# ethernet_poe.net
KiCad netlist of a schematic drawn in EAGLE
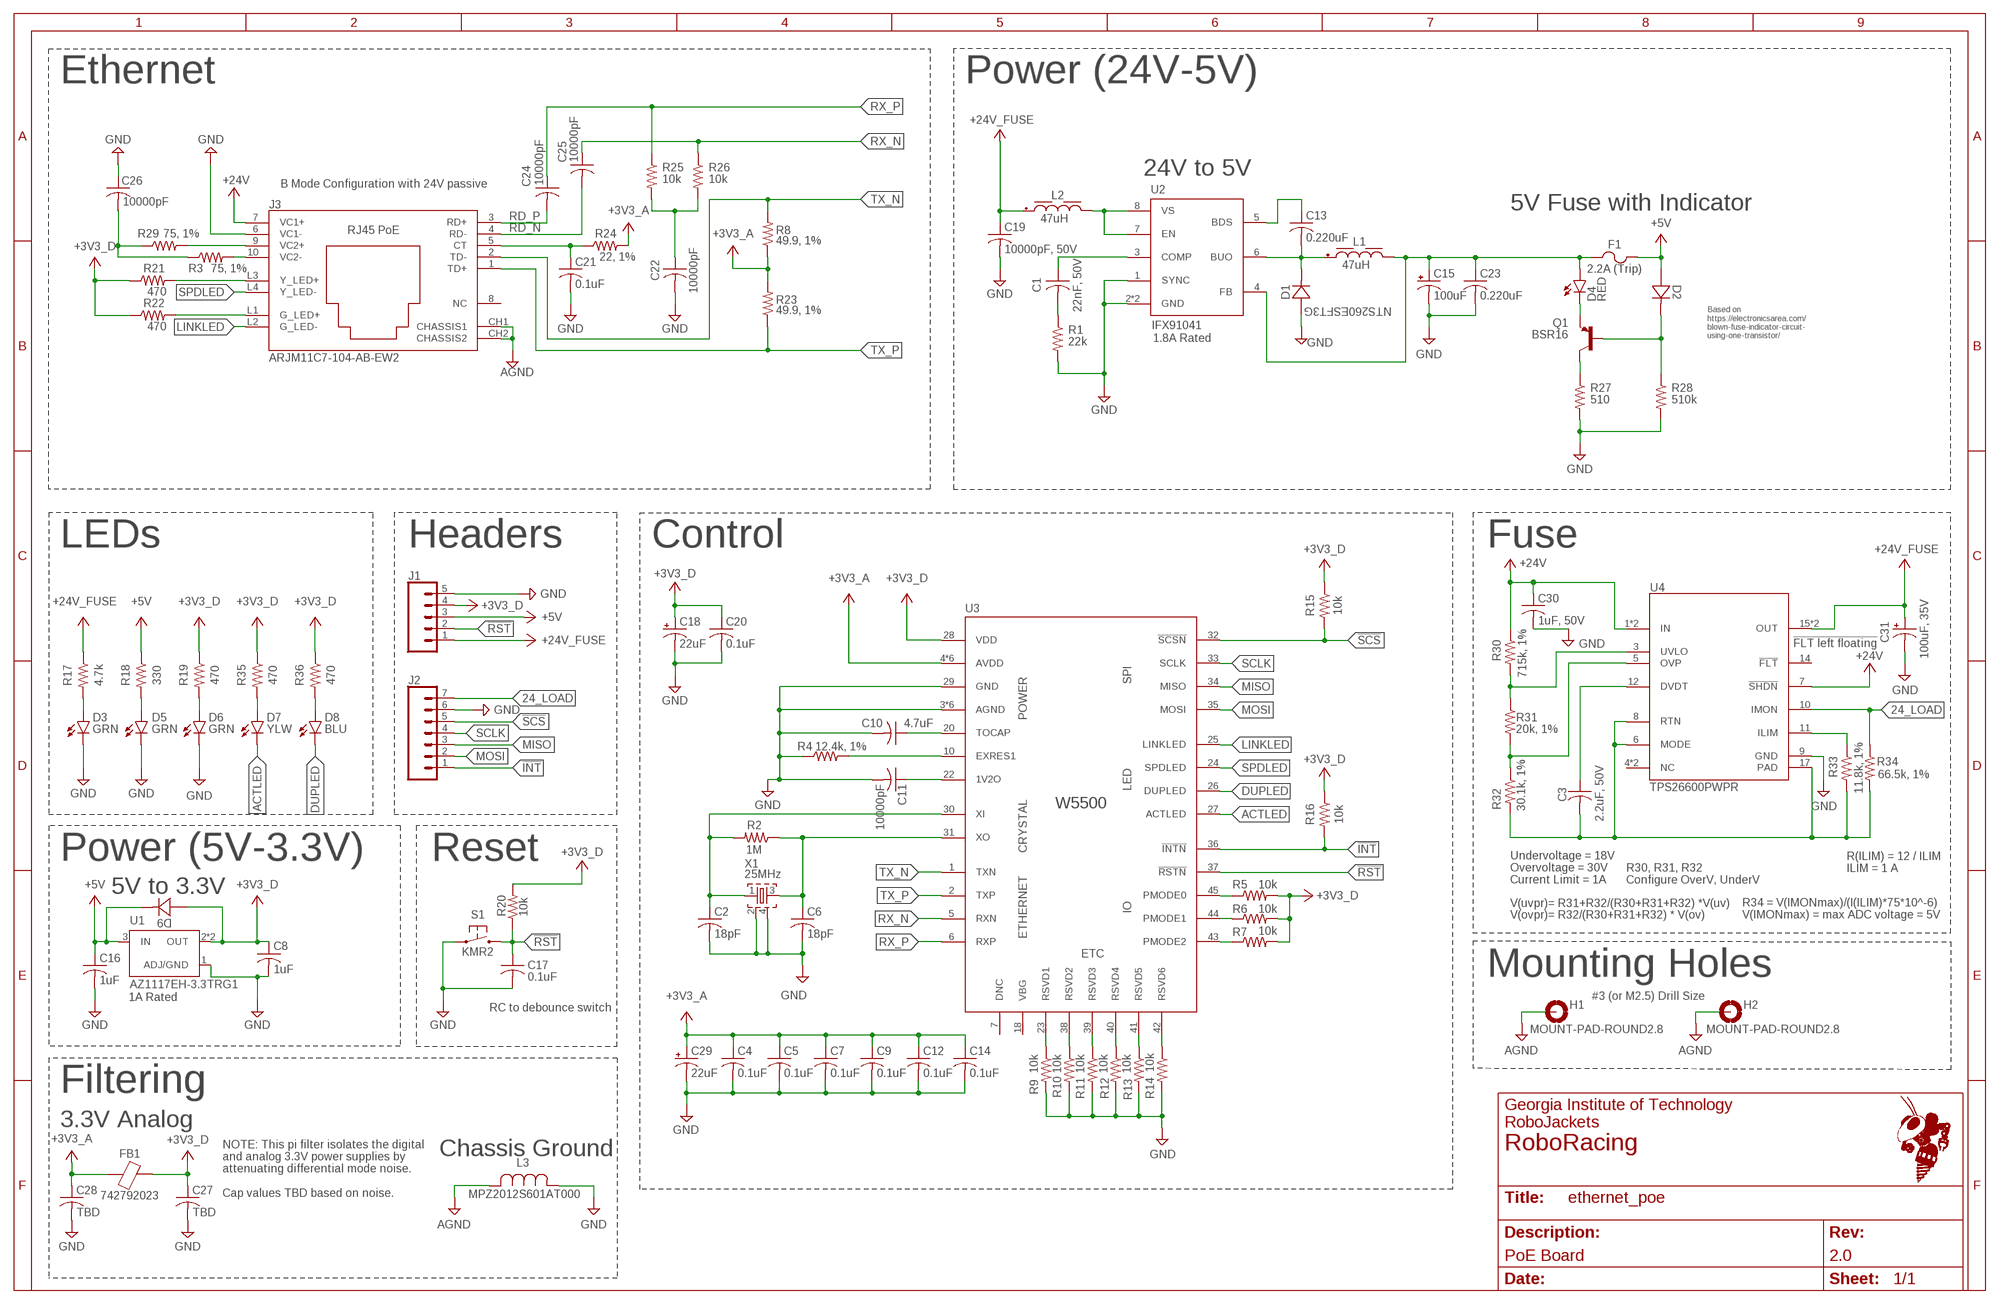
[diagram p0: schematic, sheet 1]

(export (version "E")
  (design (tool "Eeschema 10.0.6"))
  (components
    (comp (ref "C1")
      (value "22nF, 50V")
      (footprint "eagle-import:C0603")
      (libsource (lib "eagle-import") (part "rcl_334_C-USC0603"))
    )
    (comp (ref "C2")
      (value "18pF")
      (footprint "eagle-import:C0603")
      (libsource (lib "eagle-import") (part "rcl_334_C-USC0603"))
    )
    (comp (ref "C3")
      (value "2.2uF, 50V")
      (footprint "eagle-import:C0603")
      (libsource (lib "eagle-import") (part "rcl_334_C-USC0603"))
    )
    (comp (ref "C4")
      (value "0.1uF")
      (footprint "eagle-import:C0402")
      (libsource (lib "eagle-import") (part "C-USC0402"))
    )
    (comp (ref "C5")
      (value "0.1uF")
      (footprint "eagle-import:C0402")
      (libsource (lib "eagle-import") (part "C-USC0402"))
    )
    (comp (ref "C6")
      (value "18pF")
      (footprint "eagle-import:C0603")
      (libsource (lib "eagle-import") (part "rcl_334_C-USC0603"))
    )
    (comp (ref "C7")
      (value "0.1uF")
      (footprint "eagle-import:C0402")
      (libsource (lib "eagle-import") (part "C-USC0402"))
    )
    (comp (ref "C8")
      (value "1uF")
      (footprint "eagle-import:C0603")
      (libsource (lib "eagle-import") (part "rcl_334_C-USC0603"))
    )
    (comp (ref "C9")
      (value "0.1uF")
      (footprint "eagle-import:C0402")
      (libsource (lib "eagle-import") (part "C-USC0402"))
    )
    (comp (ref "C10")
      (value "4.7uF")
      (footprint "eagle-import:C0603")
      (libsource (lib "eagle-import") (part "rcl_334_C-USC0603"))
    )
    (comp (ref "C11")
      (value "10000pF")
      (footprint "eagle-import:C0402")
      (libsource (lib "eagle-import") (part "C-USC0402"))
    )
    (comp (ref "C12")
      (value "0.1uF")
      (footprint "eagle-import:C0402")
      (libsource (lib "eagle-import") (part "C-USC0402"))
    )
    (comp (ref "C13")
      (value "0.220uF")
      (footprint "eagle-import:C0603")
      (libsource (lib "eagle-import") (part "rcl_334_C-USC0603"))
    )
    (comp (ref "C14")
      (value "0.1uF")
      (footprint "eagle-import:C0402")
      (libsource (lib "eagle-import") (part "C-USC0402"))
    )
    (comp (ref "C15")
      (value "100uF")
      (footprint "eagle-import:E2-5")
      (libsource (lib "eagle-import") (part "CPOL-USE2-5"))
    )
    (comp (ref "C16")
      (value "1uF")
      (footprint "eagle-import:C0603")
      (libsource (lib "eagle-import") (part "rcl_334_C-USC0603"))
    )
    (comp (ref "C17")
      (value "0.1uF")
      (footprint "eagle-import:C0603")
      (libsource (lib "eagle-import") (part "rcl_334_C-USC0603"))
    )
    (comp (ref "C18")
      (value "22uF")
      (footprint "eagle-import:E2-5")
      (libsource (lib "eagle-import") (part "CPOL-USE2-5"))
    )
    (comp (ref "C19")
      (value "10000pF, 50V")
      (footprint "eagle-import:C0603")
      (libsource (lib "eagle-import") (part "rcl_334_C-USC0603"))
    )
    (comp (ref "C20")
      (value "0.1uF")
      (footprint "eagle-import:C0603")
      (libsource (lib "eagle-import") (part "rcl_334_C-USC0603"))
    )
    (comp (ref "C21")
      (value "0.1uF")
      (footprint "eagle-import:C0603")
      (libsource (lib "eagle-import") (part "rcl_334_C-USC0603"))
    )
    (comp (ref "C22")
      (value "10000pF")
      (footprint "eagle-import:C0603")
      (libsource (lib "eagle-import") (part "rcl_334_C-USC0603"))
    )
    (comp (ref "C23")
      (value "0.220uF")
      (footprint "eagle-import:C0603")
      (libsource (lib "eagle-import") (part "rcl_334_C-USC0603"))
    )
    (comp (ref "C24")
      (value "10000pF")
      (footprint "eagle-import:C0402")
      (libsource (lib "eagle-import") (part "C-USC0402"))
    )
    (comp (ref "C25")
      (value "10000pF")
      (footprint "eagle-import:C0402")
      (libsource (lib "eagle-import") (part "C-USC0402"))
    )
    (comp (ref "C26")
      (value "10000pF")
      (footprint "eagle-import:C0603")
      (libsource (lib "eagle-import") (part "rcl_334_C-USC0603"))
    )
    (comp (ref "C27")
      (value "TBD")
      (footprint "eagle-import:C0603")
      (libsource (lib "eagle-import") (part "C-USC0603"))
    )
    (comp (ref "C28")
      (value "TBD")
      (footprint "eagle-import:C0603")
      (libsource (lib "eagle-import") (part "C-USC0603"))
    )
    (comp (ref "C29")
      (value "22uF")
      (footprint "eagle-import:PANASONIC_C")
      (libsource (lib "eagle-import") (part "22UF-POLAR-PANASONIC_C-35V-20%"))
    )
    (comp (ref "C30")
      (value "1uF, 50V")
      (footprint "eagle-import:C0603")
      (libsource (lib "eagle-import") (part "rcl_334_C-USC0603"))
    )
    (comp (ref "C31")
      (value "100uF, 35V")
      (footprint "eagle-import:E2-5")
      (libsource (lib "eagle-import") (part "CPOL-USE2-5"))
    )
    (comp (ref "D1")
      (value "NTS260ESFT3G")
      (footprint "eagle-import:DIO_SS26FL")
      (libsource (lib "eagle-import") (part "NTS260ESFT3G"))
    )
    (comp (ref "D2")
      (value "1N4148W-7-F")
      (footprint "eagle-import:SOD123_DIO")
      (libsource (lib "eagle-import") (part "1N4148W-7-F"))
    )
    (comp (ref "D3")
      (value "GRN")
      (footprint "eagle-import:CHIP-LED0603")
      (libsource (lib "eagle-import") (part "LEDCHIP-LED0603"))
    )
    (comp (ref "D4")
      (value "RED")
      (footprint "eagle-import:CHIP-LED0603")
      (libsource (lib "eagle-import") (part "LEDCHIP-LED0603"))
    )
    (comp (ref "D5")
      (value "GRN")
      (footprint "eagle-import:CHIP-LED0603")
      (libsource (lib "eagle-import") (part "LEDCHIP-LED0603"))
    )
    (comp (ref "D6")
      (value "GRN")
      (footprint "eagle-import:CHIP-LED0603")
      (libsource (lib "eagle-import") (part "LEDCHIP-LED0603"))
    )
    (comp (ref "D7")
      (value "YLW")
      (footprint "eagle-import:CHIP-LED0603")
      (libsource (lib "eagle-import") (part "LEDCHIP-LED0603"))
    )
    (comp (ref "D8")
      (value "BLU")
      (footprint "eagle-import:CHIP-LED0603")
      (libsource (lib "eagle-import") (part "LEDCHIP-LED0603"))
    )
    (comp (ref "D9")
      (value "1N4148W-7-F")
      (footprint "eagle-import:SOD123_DIO")
      (libsource (lib "eagle-import") (part "1N4148W-7-F"))
    )
    (comp (ref "F1")
      (value "2.2A (Trip)")
      (footprint "eagle-import:0ZCG_BEL")
      (libsource (lib "eagle-import") (part "0ZCG0110AF2C"))
    )
    (comp (ref "FB1")
      (value "742792023")
      (footprint "eagle-import:0805")
      (libsource (lib "eagle-import") (part "742792023"))
    )
    (comp (ref "H1")
      (value "MOUNT-PAD-ROUND2.8")
      (footprint "eagle-import:2,8-PAD")
      (libsource (lib "eagle-import") (part "MOUNT-PAD-ROUND2.8"))
    )
    (comp (ref "H2")
      (value "MOUNT-PAD-ROUND2.8")
      (footprint "eagle-import:2,8-PAD")
      (libsource (lib "eagle-import") (part "MOUNT-PAD-ROUND2.8"))
    )
    (comp (ref "J1")
      (value "CONN_05")
      (footprint "eagle-import:1X05")
      (libsource (lib "eagle-import") (part "CONN_05"))
    )
    (comp (ref "J2")
      (value "CONN_07")
      (footprint "eagle-import:1X07")
      (libsource (lib "eagle-import") (part "CONN_07"))
    )
    (comp (ref "J3")
      (value "ARJM11C7-104-AB-EW2")
      (footprint "eagle-import:CONN_EW_ABR")
      (libsource (lib "eagle-import") (part "ARJM11C7-104-AB-EW2"))
    )
    (comp (ref "L1")
      (value "47uH")
      (footprint "eagle-import:WE-PD_1260")
      (libsource (lib "eagle-import") (part "WE-PD_1260_744771147"))
    )
    (comp (ref "L2")
      (value "47uH")
      (footprint "eagle-import:WE-PD_7345")
      (libsource (lib "eagle-import") (part "WE-PD_7345_744777147"))
    )
    (comp (ref "L3")
      (value "MPZ2012S601AT000")
      (footprint "eagle-import:IND_2012_TDK")
      (libsource (lib "eagle-import") (part "MPZ2012S601AT000"))
    )
    (comp (ref "Q1")
      (value "BSR16")
      (footprint "eagle-import:SOT-23-3")
      (libsource (lib "eagle-import") (part "BSR16"))
    )
    (comp (ref "R1")
      (value "22k")
      (footprint "eagle-import:R0603")
      (libsource (lib "eagle-import") (part "rcl_334_R-US_R0603"))
    )
    (comp (ref "R2")
      (value "1M")
      (footprint "eagle-import:R0402")
      (libsource (lib "eagle-import") (part "R-US_R0402"))
    )
    (comp (ref "R3")
      (value "75, 1%")
      (footprint "eagle-import:R0603")
      (libsource (lib "eagle-import") (part "rcl_334_R-US_R0603"))
    )
    (comp (ref "R4")
      (value "12.4k, 1%")
      (footprint "eagle-import:R0603")
      (libsource (lib "eagle-import") (part "rcl_334_R-US_R0603"))
    )
    (comp (ref "R5")
      (value "10k")
      (footprint "eagle-import:R0603")
      (libsource (lib "eagle-import") (part "rcl_334_R-US_R0603"))
    )
    (comp (ref "R6")
      (value "10k")
      (footprint "eagle-import:R0603")
      (libsource (lib "eagle-import") (part "rcl_334_R-US_R0603"))
    )
    (comp (ref "R7")
      (value "10k")
      (footprint "eagle-import:R0603")
      (libsource (lib "eagle-import") (part "rcl_334_R-US_R0603"))
    )
    (comp (ref "R8")
      (value "49.9, 1%")
      (footprint "eagle-import:R0402")
      (libsource (lib "eagle-import") (part "R-US_R0402"))
    )
    (comp (ref "R9")
      (value "10k")
      (footprint "eagle-import:R0603")
      (libsource (lib "eagle-import") (part "rcl_334_R-US_R0603"))
    )
    (comp (ref "R10")
      (value "10k")
      (footprint "eagle-import:R0603")
      (libsource (lib "eagle-import") (part "rcl_334_R-US_R0603"))
    )
    (comp (ref "R11")
      (value "10k")
      (footprint "eagle-import:R0603")
      (libsource (lib "eagle-import") (part "rcl_334_R-US_R0603"))
    )
    (comp (ref "R12")
      (value "10k")
      (footprint "eagle-import:R0603")
      (libsource (lib "eagle-import") (part "rcl_334_R-US_R0603"))
    )
    (comp (ref "R13")
      (value "10k")
      (footprint "eagle-import:R0603")
      (libsource (lib "eagle-import") (part "rcl_334_R-US_R0603"))
    )
    (comp (ref "R14")
      (value "10k")
      (footprint "eagle-import:R0603")
      (libsource (lib "eagle-import") (part "rcl_334_R-US_R0603"))
    )
    (comp (ref "R15")
      (value "10k")
      (footprint "eagle-import:R0603")
      (libsource (lib "eagle-import") (part "rcl_334_R-US_R0603"))
    )
    (comp (ref "R16")
      (value "10k")
      (footprint "eagle-import:R0603")
      (libsource (lib "eagle-import") (part "rcl_334_R-US_R0603"))
    )
    (comp (ref "R17")
      (value "4.7k")
      (footprint "eagle-import:R0603")
      (libsource (lib "eagle-import") (part "rcl_334_R-US_R0603"))
    )
    (comp (ref "R18")
      (value "330")
      (footprint "eagle-import:R0603")
      (libsource (lib "eagle-import") (part "rcl_334_R-US_R0603"))
    )
    (comp (ref "R19")
      (value "470")
      (footprint "eagle-import:R0603")
      (libsource (lib "eagle-import") (part "rcl_334_R-US_R0603"))
    )
    (comp (ref "R20")
      (value "10k")
      (footprint "eagle-import:R0603")
      (libsource (lib "eagle-import") (part "rcl_334_R-US_R0603"))
    )
    (comp (ref "R21")
      (value "470")
      (footprint "eagle-import:R0603")
      (libsource (lib "eagle-import") (part "rcl_334_R-US_R0603"))
    )
    (comp (ref "R22")
      (value "470")
      (footprint "eagle-import:R0603")
      (libsource (lib "eagle-import") (part "rcl_334_R-US_R0603"))
    )
    (comp (ref "R23")
      (value "49.9, 1%")
      (footprint "eagle-import:R0402")
      (libsource (lib "eagle-import") (part "R-US_R0402"))
    )
    (comp (ref "R24")
      (value "22, 1%")
      (footprint "eagle-import:R0603")
      (libsource (lib "eagle-import") (part "rcl_334_R-US_R0603"))
    )
    (comp (ref "R25")
      (value "10k")
      (footprint "eagle-import:R0603")
      (libsource (lib "eagle-import") (part "rcl_334_R-US_R0603"))
    )
    (comp (ref "R26")
      (value "10k")
      (footprint "eagle-import:R0603")
      (libsource (lib "eagle-import") (part "rcl_334_R-US_R0603"))
    )
    (comp (ref "R27")
      (value "510")
      (footprint "eagle-import:R0603")
      (libsource (lib "eagle-import") (part "rcl_334_R-US_R0603"))
    )
    (comp (ref "R28")
      (value "510k")
      (footprint "eagle-import:R0603")
      (libsource (lib "eagle-import") (part "rcl_334_R-US_R0603"))
    )
    (comp (ref "R29")
      (value "75, 1%")
      (footprint "eagle-import:R0603")
      (libsource (lib "eagle-import") (part "rcl_334_R-US_R0603"))
    )
    (comp (ref "R30")
      (value "715k, 1%")
      (footprint "eagle-import:R0603")
      (libsource (lib "eagle-import") (part "rcl_334_R-US_R0603"))
    )
    (comp (ref "R31")
      (value "20k, 1%")
      (footprint "eagle-import:R0603")
      (libsource (lib "eagle-import") (part "rcl_334_R-US_R0603"))
    )
    (comp (ref "R32")
      (value "30.1k, 1%")
      (footprint "eagle-import:R0603")
      (libsource (lib "eagle-import") (part "rcl_334_R-US_R0603"))
    )
    (comp (ref "R33")
      (value "11.8k, 1%")
      (footprint "eagle-import:R0603")
      (libsource (lib "eagle-import") (part "rcl_334_R-US_R0603"))
    )
    (comp (ref "R34")
      (value "66.5k, 1%")
      (footprint "eagle-import:R0603")
      (libsource (lib "eagle-import") (part "rcl_334_R-US_R0603"))
    )
    (comp (ref "R35")
      (value "470")
      (footprint "eagle-import:R0603")
      (libsource (lib "eagle-import") (part "rcl_334_R-US_R0603"))
    )
    (comp (ref "R36")
      (value "470")
      (footprint "eagle-import:R0603")
      (libsource (lib "eagle-import") (part "rcl_334_R-US_R0603"))
    )
    (comp (ref "S1")
      (value "KMR2")
      (footprint "eagle-import:KMR2")
      (libsource (lib "eagle-import") (part "KMR2"))
    )
    (comp (ref "U1")
      (value "AZ1117EH-3.3TRG1")
      (footprint "eagle-import:SOT230P700X180-4N")
      (libsource (lib "eagle-import") (part "AZ1117EH-3.3TRG1"))
    )
    (comp (ref "U2")
      (value "IFX91041")
      (footprint "eagle-import:SOIC-8-EXPOSED_PAD")
      (libsource (lib "eagle-import") (part "IFX91041"))
    )
    (comp (ref "U3")
      (value "W5500")
      (footprint "eagle-import:48-LQFP")
      (libsource (lib "eagle-import") (part "W5500"))
    )
    (comp (ref "U4")
      (value "TPS26600PWPR")
      (footprint "eagle-import:PWP0016H_N")
      (libsource (lib "eagle-import") (part "TPS26600PWPR"))
    )
    (comp (ref "X1")
      (value "25MHz")
      (footprint "eagle-import:OSCILLATOR-SMD-2.5X2")
      (libsource (lib "eagle-import") (part "ABM10-25.000MHZ-18-E30-T3"))
    )
  )
  (nets
    (net (code "1") (name "+3V3_A") (class "Default")
      (node (ref "C12") (pin "1") (pinfunction "1_1") (pintype "passive"))
      (node (ref "C14") (pin "1") (pinfunction "1_1") (pintype "passive"))
      (node (ref "C28") (pin "1") (pinfunction "1_1") (pintype "passive"))
      (node (ref "C29") (pin "+") (pinfunction "+_+") (pintype "passive"))
      (node (ref "C4") (pin "1") (pinfunction "1_1") (pintype "passive"))
      (node (ref "C5") (pin "1") (pinfunction "1_1") (pintype "passive"))
      (node (ref "C7") (pin "1") (pinfunction "1_1") (pintype "passive"))
      (node (ref "C9") (pin "1") (pinfunction "1_1") (pintype "passive"))
      (node (ref "FB1") (pin "1") (pinfunction "1_1") (pintype "passive"))
      (node (ref "R23") (pin "2") (pinfunction "2_2") (pintype "passive"))
      (node (ref "R24") (pin "2") (pinfunction "2_2") (pintype "passive"))
      (node (ref "R8") (pin "1") (pinfunction "1_1") (pintype "passive"))
      (node (ref "U3") (pin "11") (pinfunction "AVDD_11") (pintype "power_in"))
      (node (ref "U3") (pin "15") (pinfunction "AVDD_15") (pintype "power_in"))
      (node (ref "U3") (pin "17") (pinfunction "AVDD_17") (pintype "power_in"))
      (node (ref "U3") (pin "21") (pinfunction "AVDD_21") (pintype "power_in"))
      (node (ref "U3") (pin "4") (pinfunction "AVDD_4") (pintype "power_in"))
      (node (ref "U3") (pin "8") (pinfunction "AVDD_8") (pintype "power_in"))
    )
    (net (code "2") (name "+3V3_D") (class "Default")
      (node (ref "C18") (pin "+") (pinfunction "+_+") (pintype "passive"))
      (node (ref "C20") (pin "1") (pinfunction "1_1") (pintype "passive"))
      (node (ref "C27") (pin "1") (pinfunction "1_1") (pintype "passive"))
      (node (ref "C8") (pin "1") (pinfunction "1_1") (pintype "passive"))
      (node (ref "D9") (pin "2") (pinfunction "2_2") (pintype "passive"))
      (node (ref "FB1") (pin "2") (pinfunction "2_2") (pintype "passive"))
      (node (ref "J1") (pin "4") (pinfunction "4_4") (pintype "passive"))
      (node (ref "R15") (pin "1") (pinfunction "1_1") (pintype "passive"))
      (node (ref "R16") (pin "1") (pinfunction "1_1") (pintype "passive"))
      (node (ref "R19") (pin "1") (pinfunction "1_1") (pintype "passive"))
      (node (ref "R20") (pin "2") (pinfunction "2_2") (pintype "passive"))
      (node (ref "R21") (pin "1") (pinfunction "1_1") (pintype "passive"))
      (node (ref "R22") (pin "1") (pinfunction "1_1") (pintype "passive"))
      (node (ref "R35") (pin "1") (pinfunction "1_1") (pintype "passive"))
      (node (ref "R36") (pin "1") (pinfunction "1_1") (pintype "passive"))
      (node (ref "R5") (pin "2") (pinfunction "2_2") (pintype "passive"))
      (node (ref "R6") (pin "2") (pinfunction "2_2") (pintype "passive"))
      (node (ref "R7") (pin "2") (pinfunction "2_2") (pintype "passive"))
      (node (ref "U1") (pin "2") (pinfunction "OUT_2") (pintype "output"))
      (node (ref "U1") (pin "4") (pinfunction "OUT_4") (pintype "output"))
      (node (ref "U3") (pin "28") (pinfunction "VDD_28") (pintype "power_in"))
    )
    (net (code "3") (name "+5V") (class "Default")
      (node (ref "C16") (pin "1") (pinfunction "1_1") (pintype "passive"))
      (node (ref "D2") (pin "2") (pinfunction "2_2") (pintype "passive"))
      (node (ref "D9") (pin "1") (pinfunction "1_1") (pintype "passive"))
      (node (ref "F1") (pin "2") (pinfunction "2_2") (pintype "passive"))
      (node (ref "J1") (pin "3") (pinfunction "3_3") (pintype "passive"))
      (node (ref "R18") (pin "1") (pinfunction "1_1") (pintype "passive"))
      (node (ref "U1") (pin "3") (pinfunction "IN_3") (pintype "input"))
    )
    (net (code "4") (name "+24V") (class "Default")
      (node (ref "C30") (pin "1") (pinfunction "1_1") (pintype "passive"))
      (node (ref "J3") (pin "7") (pinfunction "VC1+_7") (pintype "passive"))
      (node (ref "R30") (pin "1") (pinfunction "1_1") (pintype "passive"))
      (node (ref "U4") (pin "1") (pinfunction "IN_1") (pintype "power_in"))
      (node (ref "U4") (pin "2") (pinfunction "IN_2") (pintype "power_in"))
      (node (ref "U4") (pin "7") (pinfunction "~{SHDN}_7") (pintype "input"))
    )
    (net (code "5") (name "+24V_FUSE") (class "Default")
      (node (ref "C19") (pin "1") (pinfunction "1_1") (pintype "passive"))
      (node (ref "C31") (pin "+") (pinfunction "+_+") (pintype "passive"))
      (node (ref "J1") (pin "1") (pinfunction "1_1") (pintype "passive"))
      (node (ref "L2") (pin "1") (pinfunction "1_1") (pintype "passive"))
      (node (ref "R17") (pin "1") (pinfunction "1_1") (pintype "passive"))
      (node (ref "U4") (pin "15") (pinfunction "OUT_15") (pintype "power_in"))
      (node (ref "U4") (pin "16") (pinfunction "OUT_16") (pintype "power_in"))
    )
    (net (code "6") (name "/RD_N") (class "Default")
      (node (ref "C25") (pin "2") (pinfunction "2_2") (pintype "passive"))
      (node (ref "J3") (pin "4") (pinfunction "RD-_4") (pintype "passive"))
    )
    (net (code "7") (name "/RD_P") (class "Default")
      (node (ref "C24") (pin "2") (pinfunction "2_2") (pintype "passive"))
      (node (ref "J3") (pin "3") (pinfunction "RD+_3") (pintype "passive"))
    )
    (net (code "8") (name "/~{INT}") (class "Default")
      (node (ref "J2") (pin "1") (pinfunction "1_1") (pintype "passive"))
      (node (ref "R16") (pin "2") (pinfunction "2_2") (pintype "passive"))
      (node (ref "U3") (pin "36") (pinfunction "~{INTN}_36") (pintype "output"))
    )
    (net (code "9") (name "/~{RST}") (class "Default")
      (node (ref "C17") (pin "1") (pinfunction "1_1") (pintype "passive"))
      (node (ref "J1") (pin "2") (pinfunction "2_2") (pintype "passive"))
      (node (ref "R20") (pin "1") (pinfunction "1_1") (pintype "passive"))
      (node (ref "S1") (pin "2.1") (pinfunction "2_2.1") (pintype "passive"))
      (node (ref "S1") (pin "2.2") (pinfunction "2_2.2") (pintype "passive"))
      (node (ref "U3") (pin "37") (pinfunction "~{RSTN}_37") (pintype "input"))
    )
    (net (code "10") (name "/~{SCS}") (class "Default")
      (node (ref "J2") (pin "5") (pinfunction "5_5") (pintype "passive"))
      (node (ref "R15") (pin "2") (pinfunction "2_2") (pintype "passive"))
      (node (ref "U3") (pin "32") (pinfunction "~{SCSN}_32") (pintype "input"))
    )
    (net (code "11") (name "24_LOAD") (class "Default")
      (node (ref "J2") (pin "7") (pinfunction "7_7") (pintype "passive"))
      (node (ref "R34") (pin "1") (pinfunction "1_1") (pintype "passive"))
      (node (ref "U4") (pin "10") (pinfunction "IMON_10") (pintype "output"))
    )
    (net (code "12") (name "ACTLED") (class "Default")
      (node (ref "D7") (pin "C") (pinfunction "C_C") (pintype "passive"))
      (node (ref "U3") (pin "27") (pinfunction "ACTLED_27") (pintype "output"))
    )
    (net (code "13") (name "AGND") (class "Default")
      (node (ref "H1") (pin "B2,8") (pinfunction "MOUNT_B2,8") (pintype "passive"))
      (node (ref "H2") (pin "B2,8") (pinfunction "MOUNT_B2,8") (pintype "passive"))
      (node (ref "J3") (pin "CH1") (pinfunction "CHASSIS1_CH1") (pintype "passive"))
      (node (ref "J3") (pin "CH2") (pinfunction "CHASSIS2_CH2") (pintype "passive"))
      (node (ref "L3") (pin "2") (pinfunction "2_2") (pintype "passive"))
    )
    (net (code "14") (name "DUPLED") (class "Default")
      (node (ref "D8") (pin "C") (pinfunction "C_C") (pintype "passive"))
      (node (ref "U3") (pin "26") (pinfunction "DUPLED_26") (pintype "output"))
    )
    (net (code "15") (name "GND") (class "Default")
      (node (ref "C10") (pin "2") (pinfunction "2_2") (pintype "passive"))
      (node (ref "C11") (pin "2") (pinfunction "2_2") (pintype "passive"))
      (node (ref "C12") (pin "2") (pinfunction "2_2") (pintype "passive"))
      (node (ref "C14") (pin "2") (pinfunction "2_2") (pintype "passive"))
      (node (ref "C15") (pin "-") (pinfunction "-_-") (pintype "passive"))
      (node (ref "C16") (pin "2") (pinfunction "2_2") (pintype "passive"))
      (node (ref "C17") (pin "2") (pinfunction "2_2") (pintype "passive"))
      (node (ref "C18") (pin "-") (pinfunction "-_-") (pintype "passive"))
      (node (ref "C19") (pin "2") (pinfunction "2_2") (pintype "passive"))
      (node (ref "C2") (pin "2") (pinfunction "2_2") (pintype "passive"))
      (node (ref "C20") (pin "2") (pinfunction "2_2") (pintype "passive"))
      (node (ref "C21") (pin "2") (pinfunction "2_2") (pintype "passive"))
      (node (ref "C22") (pin "2") (pinfunction "2_2") (pintype "passive"))
      (node (ref "C23") (pin "2") (pinfunction "2_2") (pintype "passive"))
      (node (ref "C26") (pin "1") (pinfunction "1_1") (pintype "passive"))
      (node (ref "C27") (pin "2") (pinfunction "2_2") (pintype "passive"))
      (node (ref "C28") (pin "2") (pinfunction "2_2") (pintype "passive"))
      (node (ref "C29") (pin "-") (pinfunction "-_-") (pintype "passive"))
      (node (ref "C30") (pin "2") (pinfunction "2_2") (pintype "passive"))
      (node (ref "C31") (pin "-") (pinfunction "-_-") (pintype "passive"))
      (node (ref "C4") (pin "2") (pinfunction "2_2") (pintype "passive"))
      (node (ref "C5") (pin "2") (pinfunction "2_2") (pintype "passive"))
      (node (ref "C6") (pin "2") (pinfunction "2_2") (pintype "passive"))
      (node (ref "C7") (pin "2") (pinfunction "2_2") (pintype "passive"))
      (node (ref "C8") (pin "2") (pinfunction "2_2") (pintype "passive"))
      (node (ref "C9") (pin "2") (pinfunction "2_2") (pintype "passive"))
      (node (ref "D1") (pin "2") (pinfunction "2_2") (pintype "passive"))
      (node (ref "D3") (pin "C") (pinfunction "C_C") (pintype "passive"))
      (node (ref "D5") (pin "C") (pinfunction "C_C") (pintype "passive"))
      (node (ref "D6") (pin "C") (pinfunction "C_C") (pintype "passive"))
      (node (ref "J1") (pin "5") (pinfunction "5_5") (pintype "passive"))
      (node (ref "J2") (pin "6") (pinfunction "6_6") (pintype "passive"))
      (node (ref "J3") (pin "6") (pinfunction "VC1-_6") (pintype "passive"))
      (node (ref "L3") (pin "1") (pinfunction "1_1") (pintype "passive"))
      (node (ref "R1") (pin "2") (pinfunction "2_2") (pintype "passive"))
      (node (ref "R10") (pin "2") (pinfunction "2_2") (pintype "passive"))
      (node (ref "R11") (pin "2") (pinfunction "2_2") (pintype "passive"))
      (node (ref "R12") (pin "2") (pinfunction "2_2") (pintype "passive"))
      (node (ref "R13") (pin "2") (pinfunction "2_2") (pintype "passive"))
      (node (ref "R14") (pin "2") (pinfunction "2_2") (pintype "passive"))
      (node (ref "R27") (pin "2") (pinfunction "2_2") (pintype "passive"))
      (node (ref "R28") (pin "2") (pinfunction "2_2") (pintype "passive"))
      (node (ref "R4") (pin "1") (pinfunction "1_1") (pintype "passive"))
      (node (ref "R9") (pin "2") (pinfunction "2_2") (pintype "passive"))
      (node (ref "S1") (pin "1.1") (pinfunction "1_1.1") (pintype "passive"))
      (node (ref "S1") (pin "1.2") (pinfunction "1_1.2") (pintype "passive"))
      (node (ref "U1") (pin "1") (pinfunction "ADJ/GND_1") (pintype "power_in"))
      (node (ref "U2") (pin "1") (pinfunction "SYNC_1") (pintype "input"))
      (node (ref "U2") (pin "2") (pinfunction "GND_2") (pintype "power_in"))
      (node (ref "U2") (pin "9") (pinfunction "GND_9") (pintype "power_in"))
      (node (ref "U3") (pin "14") (pinfunction "AGND_14") (pintype "power_in"))
      (node (ref "U3") (pin "16") (pinfunction "AGND_16") (pintype "power_in"))
      (node (ref "U3") (pin "19") (pinfunction "AGND_19") (pintype "power_in"))
      (node (ref "U3") (pin "29") (pinfunction "GND_29") (pintype "power_in"))
      (node (ref "U3") (pin "3") (pinfunction "AGND_3") (pintype "power_in"))
      (node (ref "U3") (pin "48") (pinfunction "AGND_48") (pintype "power_in"))
      (node (ref "U3") (pin "9") (pinfunction "AGND_9") (pintype "power_in"))
      (node (ref "U4") (pin "9") (pinfunction "GND_9") (pintype "power_in"))
      (node (ref "X1") (pin "2") (pinfunction "SHD1_2") (pintype "passive"))
      (node (ref "X1") (pin "4") (pinfunction "SHD2_4") (pintype "passive"))
    )
    (net (code "16") (name "LINKLED") (class "Default")
      (node (ref "J3") (pin "L2") (pinfunction "G_LED-_L2") (pintype "passive"))
      (node (ref "U3") (pin "25") (pinfunction "LINKLED_25") (pintype "output"))
    )
    (net (code "17") (name "MISO") (class "Default")
      (node (ref "J2") (pin "3") (pinfunction "3_3") (pintype "passive"))
      (node (ref "U3") (pin "34") (pinfunction "MISO_34") (pintype "output"))
    )
    (net (code "18") (name "MOSI") (class "Default")
      (node (ref "J2") (pin "2") (pinfunction "2_2") (pintype "passive"))
      (node (ref "U3") (pin "35") (pinfunction "MOSI_35") (pintype "input"))
    )
    (net (code "19") (name "Net-(C1-Pad2)") (class "Default")
      (node (ref "C1") (pin "2") (pinfunction "2_2") (pintype "passive"))
      (node (ref "R1") (pin "1") (pinfunction "1_1") (pintype "passive"))
    )
    (net (code "20") (name "Net-(C22-Pad1)") (class "Default")
      (node (ref "C22") (pin "1") (pinfunction "1_1") (pintype "passive"))
      (node (ref "R25") (pin "2") (pinfunction "2_2") (pintype "passive"))
      (node (ref "R26") (pin "2") (pinfunction "2_2") (pintype "passive"))
    )
    (net (code "21") (name "Net-(C26-Pad2)") (class "Default")
      (node (ref "C26") (pin "2") (pinfunction "2_2") (pintype "passive"))
      (node (ref "R29") (pin "1") (pinfunction "1_1") (pintype "passive"))
      (node (ref "R3") (pin "1") (pinfunction "1_1") (pintype "passive"))
    )
    (net (code "22") (name "Net-(D3-PadA)") (class "Default")
      (node (ref "D3") (pin "A") (pinfunction "A_A") (pintype "passive"))
      (node (ref "R17") (pin "2") (pinfunction "2_2") (pintype "passive"))
    )
    (net (code "23") (name "Net-(D5-PadA)") (class "Default")
      (node (ref "D5") (pin "A") (pinfunction "A_A") (pintype "passive"))
      (node (ref "R18") (pin "2") (pinfunction "2_2") (pintype "passive"))
    )
    (net (code "24") (name "Net-(D6-PadA)") (class "Default")
      (node (ref "D6") (pin "A") (pinfunction "A_A") (pintype "passive"))
      (node (ref "R19") (pin "2") (pinfunction "2_2") (pintype "passive"))
    )
    (net (code "25") (name "Net-(D7-PadA)") (class "Default")
      (node (ref "D7") (pin "A") (pinfunction "A_A") (pintype "passive"))
      (node (ref "R35") (pin "2") (pinfunction "2_2") (pintype "passive"))
    )
    (net (code "26") (name "Net-(D8-PadA)") (class "Default")
      (node (ref "D8") (pin "A") (pinfunction "A_A") (pintype "passive"))
      (node (ref "R36") (pin "2") (pinfunction "2_2") (pintype "passive"))
    )
    (net (code "27") (name "Net-(J3-CT)") (class "Default")
      (node (ref "C21") (pin "1") (pinfunction "1_1") (pintype "passive"))
      (node (ref "J3") (pin "5") (pinfunction "CT_5") (pintype "passive"))
      (node (ref "R24") (pin "1") (pinfunction "1_1") (pintype "passive"))
    )
    (net (code "28") (name "Net-(J3-G_LED+)") (class "Default")
      (node (ref "J3") (pin "L1") (pinfunction "G_LED+_L1") (pintype "passive"))
      (node (ref "R22") (pin "2") (pinfunction "2_2") (pintype "passive"))
    )
    (net (code "29") (name "Net-(J3-VC2+)") (class "Default")
      (node (ref "J3") (pin "9") (pinfunction "VC2+_9") (pintype "passive"))
      (node (ref "R29") (pin "2") (pinfunction "2_2") (pintype "passive"))
    )
    (net (code "30") (name "Net-(J3-VC2-)") (class "Default")
      (node (ref "J3") (pin "10") (pinfunction "VC2-_10") (pintype "passive"))
      (node (ref "R3") (pin "2") (pinfunction "2_2") (pintype "passive"))
    )
    (net (code "31") (name "Net-(J3-Y_LED+)") (class "Default")
      (node (ref "J3") (pin "L3") (pinfunction "Y_LED+_L3") (pintype "passive"))
      (node (ref "R21") (pin "2") (pinfunction "2_2") (pintype "passive"))
    )
    (net (code "32") (name "Net-(Q1-B)") (class "Default")
      (node (ref "D2") (pin "1") (pinfunction "1_1") (pintype "passive"))
      (node (ref "Q1") (pin "1") (pinfunction "B_1") (pintype "passive"))
      (node (ref "R28") (pin "1") (pinfunction "1_1") (pintype "passive"))
    )
    (net (code "33") (name "Net-(Q1-C)") (class "Default")
      (node (ref "Q1") (pin "3") (pinfunction "C_3") (pintype "passive"))
      (node (ref "R27") (pin "1") (pinfunction "1_1") (pintype "passive"))
    )
    (net (code "34") (name "Net-(Q1-E)") (class "Default")
      (node (ref "D4") (pin "C") (pinfunction "C_C") (pintype "passive"))
      (node (ref "Q1") (pin "2") (pinfunction "E_2") (pintype "passive"))
    )
    (net (code "35") (name "Net-(U2-BDS)") (class "Default")
      (node (ref "C13") (pin "1") (pinfunction "1_1") (pintype "passive"))
      (node (ref "U2") (pin "5") (pinfunction "BDS_5") (pintype "bidirectional"))
    )
    (net (code "36") (name "Net-(U2-BUO)") (class "Default")
      (node (ref "C13") (pin "2") (pinfunction "2_2") (pintype "passive"))
      (node (ref "D1") (pin "1") (pinfunction "1_1") (pintype "passive"))
      (node (ref "L1") (pin "1") (pinfunction "1_1") (pintype "passive"))
      (node (ref "U2") (pin "6") (pinfunction "BUO_6") (pintype "bidirectional"))
    )
    (net (code "37") (name "Net-(U2-COMP)") (class "Default")
      (node (ref "C1") (pin "1") (pinfunction "1_1") (pintype "passive"))
      (node (ref "U2") (pin "3") (pinfunction "COMP_3") (pintype "bidirectional"))
    )
    (net (code "38") (name "Net-(U2-EN)") (class "Default")
      (node (ref "L2") (pin "2") (pinfunction "2_2") (pintype "passive"))
      (node (ref "U2") (pin "7") (pinfunction "EN_7") (pintype "input"))
      (node (ref "U2") (pin "8") (pinfunction "VS_8") (pintype "power_in"))
    )
    (net (code "39") (name "Net-(U2-FB)") (class "Default")
      (node (ref "C15") (pin "+") (pinfunction "+_+") (pintype "passive"))
      (node (ref "C23") (pin "1") (pinfunction "1_1") (pintype "passive"))
      (node (ref "D4") (pin "A") (pinfunction "A_A") (pintype "passive"))
      (node (ref "F1") (pin "1") (pinfunction "1_1") (pintype "passive"))
      (node (ref "L1") (pin "2") (pinfunction "2_2") (pintype "passive"))
      (node (ref "U2") (pin "4") (pinfunction "FB_4") (pintype "bidirectional"))
    )
    (net (code "40") (name "Net-(U3-1V2O)") (class "Default")
      (node (ref "C11") (pin "1") (pinfunction "1_1") (pintype "passive"))
      (node (ref "U3") (pin "22") (pinfunction "1V2O_22") (pintype "output"))
    )
    (net (code "41") (name "Net-(U3-EXRES1)") (class "Default")
      (node (ref "R4") (pin "2") (pinfunction "2_2") (pintype "passive"))
      (node (ref "U3") (pin "10") (pinfunction "EXRES1_10") (pintype "output"))
    )
    (net (code "42") (name "Net-(U3-PMODE0)") (class "Default")
      (node (ref "R5") (pin "1") (pinfunction "1_1") (pintype "passive"))
      (node (ref "U3") (pin "45") (pinfunction "PMODE0_45") (pintype "input"))
    )
    (net (code "43") (name "Net-(U3-PMODE1)") (class "Default")
      (node (ref "R6") (pin "1") (pinfunction "1_1") (pintype "passive"))
      (node (ref "U3") (pin "44") (pinfunction "PMODE1_44") (pintype "input"))
    )
    (net (code "44") (name "Net-(U3-PMODE2)") (class "Default")
      (node (ref "R7") (pin "1") (pinfunction "1_1") (pintype "passive"))
      (node (ref "U3") (pin "43") (pinfunction "PMODE2_43") (pintype "input"))
    )
    (net (code "45") (name "Net-(U3-RSVD1)") (class "Default")
      (node (ref "R9") (pin "1") (pinfunction "1_1") (pintype "passive"))
      (node (ref "U3") (pin "23") (pinfunction "RSVD1_23") (pintype "input"))
    )
    (net (code "46") (name "Net-(U3-RSVD2)") (class "Default")
      (node (ref "R10") (pin "1") (pinfunction "1_1") (pintype "passive"))
      (node (ref "U3") (pin "38") (pinfunction "RSVD2_38") (pintype "input"))
    )
    (net (code "47") (name "Net-(U3-RSVD3)") (class "Default")
      (node (ref "R11") (pin "1") (pinfunction "1_1") (pintype "passive"))
      (node (ref "U3") (pin "39") (pinfunction "RSVD3_39") (pintype "input"))
    )
    (net (code "48") (name "Net-(U3-RSVD4)") (class "Default")
      (node (ref "R12") (pin "1") (pinfunction "1_1") (pintype "passive"))
      (node (ref "U3") (pin "40") (pinfunction "RSVD4_40") (pintype "input"))
    )
    (net (code "49") (name "Net-(U3-RSVD5)") (class "Default")
      (node (ref "R13") (pin "1") (pinfunction "1_1") (pintype "passive"))
      (node (ref "U3") (pin "41") (pinfunction "RSVD5_41") (pintype "input"))
    )
    (net (code "50") (name "Net-(U3-RSVD6)") (class "Default")
      (node (ref "R14") (pin "1") (pinfunction "1_1") (pintype "passive"))
      (node (ref "U3") (pin "42") (pinfunction "RSVD6_42") (pintype "input"))
    )
    (net (code "51") (name "Net-(U3-TOCAP)") (class "Default")
      (node (ref "C10") (pin "1") (pinfunction "1_1") (pintype "passive"))
      (node (ref "U3") (pin "20") (pinfunction "TOCAP_20") (pintype "output"))
    )
    (net (code "52") (name "Net-(U3-XI)") (class "Default")
      (node (ref "C2") (pin "1") (pinfunction "1_1") (pintype "passive"))
      (node (ref "R2") (pin "2") (pinfunction "2_2") (pintype "passive"))
      (node (ref "U3") (pin "30") (pinfunction "XI_30") (pintype "bidirectional"))
      (node (ref "X1") (pin "1") (pinfunction "IN_1") (pintype "passive"))
    )
    (net (code "53") (name "Net-(U3-XO)") (class "Default")
      (node (ref "C6") (pin "1") (pinfunction "1_1") (pintype "passive"))
      (node (ref "R2") (pin "1") (pinfunction "1_1") (pintype "passive"))
      (node (ref "U3") (pin "31") (pinfunction "XO_31") (pintype "bidirectional"))
      (node (ref "X1") (pin "3") (pinfunction "OUT_3") (pintype "passive"))
    )
    (net (code "54") (name "Net-(U4-DVDT)") (class "Default")
      (node (ref "C3") (pin "1") (pinfunction "1_1") (pintype "passive"))
      (node (ref "U4") (pin "12") (pinfunction "DVDT_12") (pintype "input"))
    )
    (net (code "55") (name "Net-(U4-ILIM)") (class "Default")
      (node (ref "R33") (pin "1") (pinfunction "1_1") (pintype "passive"))
      (node (ref "U4") (pin "11") (pinfunction "ILIM_11") (pintype "output"))
    )
    (net (code "56") (name "Net-(U4-MODE)") (class "Default")
      (node (ref "C3") (pin "2") (pinfunction "2_2") (pintype "passive"))
      (node (ref "R32") (pin "2") (pinfunction "2_2") (pintype "passive"))
      (node (ref "R33") (pin "2") (pinfunction "2_2") (pintype "passive"))
      (node (ref "R34") (pin "2") (pinfunction "2_2") (pintype "passive"))
      (node (ref "U4") (pin "17") (pinfunction "PAD_17") (pintype "power_in"))
      (node (ref "U4") (pin "6") (pinfunction "MODE_6") (pintype "input"))
      (node (ref "U4") (pin "8") (pinfunction "RTN_8") (pintype "input"))
    )
    (net (code "57") (name "Net-(U4-OVP)") (class "Default")
      (node (ref "R31") (pin "2") (pinfunction "2_2") (pintype "passive"))
      (node (ref "R32") (pin "1") (pinfunction "1_1") (pintype "passive"))
      (node (ref "U4") (pin "5") (pinfunction "OVP_5") (pintype "input"))
    )
    (net (code "58") (name "Net-(U4-UVLO)") (class "Default")
      (node (ref "R30") (pin "2") (pinfunction "2_2") (pintype "passive"))
      (node (ref "R31") (pin "1") (pinfunction "1_1") (pintype "passive"))
      (node (ref "U4") (pin "3") (pinfunction "UVLO_3") (pintype "input"))
    )
    (net (code "59") (name "RX_N") (class "Default")
      (node (ref "C25") (pin "1") (pinfunction "1_1") (pintype "passive"))
      (node (ref "R26") (pin "1") (pinfunction "1_1") (pintype "passive"))
      (node (ref "U3") (pin "5") (pinfunction "RXN_5") (pintype "input"))
    )
    (net (code "60") (name "RX_P") (class "Default")
      (node (ref "C24") (pin "1") (pinfunction "1_1") (pintype "passive"))
      (node (ref "R25") (pin "1") (pinfunction "1_1") (pintype "passive"))
      (node (ref "U3") (pin "6") (pinfunction "RXP_6") (pintype "input"))
    )
    (net (code "61") (name "SCLK") (class "Default")
      (node (ref "J2") (pin "4") (pinfunction "4_4") (pintype "passive"))
      (node (ref "U3") (pin "33") (pinfunction "SCLK_33") (pintype "input"))
    )
    (net (code "62") (name "SPDLED") (class "Default")
      (node (ref "J3") (pin "L4") (pinfunction "Y_LED-_L4") (pintype "passive"))
      (node (ref "U3") (pin "24") (pinfunction "SPDLED_24") (pintype "output"))
    )
    (net (code "63") (name "TX_N") (class "Default")
      (node (ref "J3") (pin "2") (pinfunction "TD-_2") (pintype "passive"))
      (node (ref "R8") (pin "2") (pinfunction "2_2") (pintype "passive"))
      (node (ref "U3") (pin "1") (pinfunction "TXN_1") (pintype "output"))
    )
    (net (code "64") (name "TX_P") (class "Default")
      (node (ref "J3") (pin "1") (pinfunction "TD+_1") (pintype "passive"))
      (node (ref "R23") (pin "1") (pinfunction "1_1") (pintype "passive"))
      (node (ref "U3") (pin "2") (pinfunction "TXP_2") (pintype "output"))
    )
    (net (code "65") (name "unconnected-(J3-NC-Pad8)") (class "Default")
      (node (ref "J3") (pin "8") (pinfunction "NC_8") (pintype "no_connect"))
    )
    (net (code "66") (name "unconnected-(U3-DNC-Pad7)") (class "Default")
      (node (ref "U3") (pin "7") (pinfunction "DNC_7") (pintype "no_connect"))
    )
    (net (code "67") (name "unconnected-(U3-VBG-Pad18)") (class "Default")
      (node (ref "U3") (pin "18") (pinfunction "VBG_18") (pintype "no_connect"))
    )
    (net (code "68") (name "unconnected-(U4-NC-Pad4)") (class "Default")
      (node (ref "U4") (pin "4") (pinfunction "NC_4") (pintype "no_connect"))
    )
    (net (code "69") (name "unconnected-(U4-NC-Pad13)") (class "Default")
      (node (ref "U4") (pin "13") (pinfunction "NC_13") (pintype "no_connect"))
    )
    (net (code "70") (name "unconnected-(U4-~{FLT}-Pad14)") (class "Default")
      (node (ref "U4") (pin "14") (pinfunction "~{FLT}_14") (pintype "open_collector"))
    )
  )
)
